# eskema_board_programacion.net
KiCad netlist of a schematic drawn in EAGLE
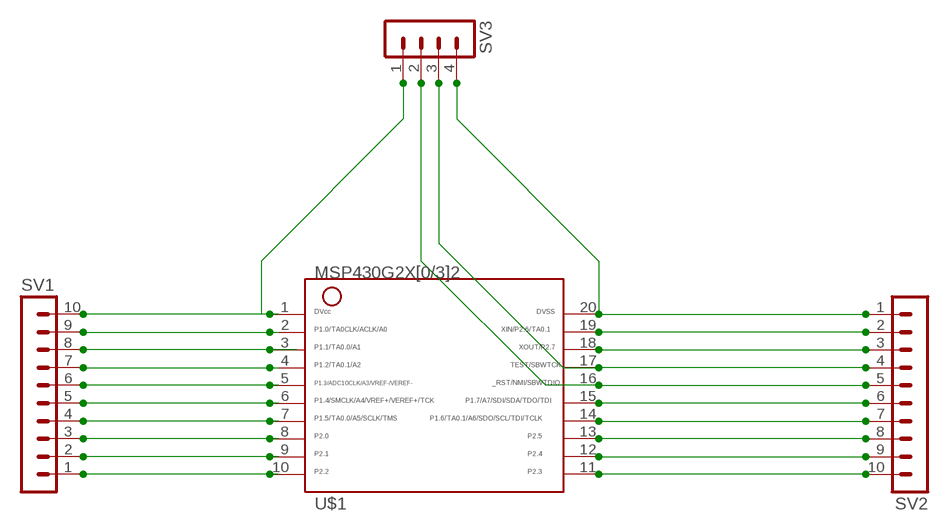
[diagram p0: schematic, sheet 1]

(export (version "E")
  (design (tool "Eeschema 10.0.6"))
  (components
    (comp (ref "SV1")
      (value "MA10-1")
      (footprint "eagle-import:MA10-1")
      (libsource (lib "eagle-import") (part "MA10-1"))
    )
    (comp (ref "SV2")
      (value "MA10-1")
      (footprint "eagle-import:MA10-1")
      (libsource (lib "eagle-import") (part "MA10-1"))
    )
    (comp (ref "SV3")
      (value "MA04-1")
      (footprint "eagle-import:MA04-1")
      (libsource (lib "eagle-import") (part "MA04-1"))
    )
    (comp (ref "U$1")
      (value "G2X[0/3]2---N20")
      (footprint "eagle-import:N20")
      (libsource (lib "eagle-import") (part "G2X[0/3]2---N20"))
    )
  )
  (nets
    (net (code "1") (name "Net-(SV1-Pad1)") (class "Default")
      (node (ref "SV1") (pin "1") (pinfunction "1_1") (pintype "passive"))
      (node (ref "U$1") (pin "10") (pinfunction "10_10") (pintype "bidirectional"))
    )
    (net (code "2") (name "Net-(SV1-Pad2)") (class "Default")
      (node (ref "SV1") (pin "2") (pinfunction "2_2") (pintype "passive"))
      (node (ref "U$1") (pin "9") (pinfunction "9_9") (pintype "bidirectional"))
    )
    (net (code "3") (name "Net-(SV1-Pad3)") (class "Default")
      (node (ref "SV1") (pin "3") (pinfunction "3_3") (pintype "passive"))
      (node (ref "U$1") (pin "8") (pinfunction "8_8") (pintype "bidirectional"))
    )
    (net (code "4") (name "Net-(SV1-Pad4)") (class "Default")
      (node (ref "SV1") (pin "4") (pinfunction "4_4") (pintype "passive"))
      (node (ref "U$1") (pin "7") (pinfunction "7_7") (pintype "bidirectional"))
    )
    (net (code "5") (name "Net-(SV1-Pad5)") (class "Default")
      (node (ref "SV1") (pin "5") (pinfunction "5_5") (pintype "passive"))
      (node (ref "U$1") (pin "6") (pinfunction "6_6") (pintype "bidirectional"))
    )
    (net (code "6") (name "Net-(SV1-Pad6)") (class "Default")
      (node (ref "SV1") (pin "6") (pinfunction "6_6") (pintype "passive"))
      (node (ref "U$1") (pin "5") (pinfunction "5_5") (pintype "bidirectional"))
    )
    (net (code "7") (name "Net-(SV1-Pad7)") (class "Default")
      (node (ref "SV1") (pin "7") (pinfunction "7_7") (pintype "passive"))
      (node (ref "U$1") (pin "4") (pinfunction "4_4") (pintype "bidirectional"))
    )
    (net (code "8") (name "Net-(SV1-Pad8)") (class "Default")
      (node (ref "SV1") (pin "8") (pinfunction "8_8") (pintype "passive"))
      (node (ref "U$1") (pin "3") (pinfunction "3_3") (pintype "bidirectional"))
    )
    (net (code "9") (name "Net-(SV1-Pad9)") (class "Default")
      (node (ref "SV1") (pin "9") (pinfunction "9_9") (pintype "passive"))
      (node (ref "U$1") (pin "2") (pinfunction "2_2") (pintype "bidirectional"))
    )
    (net (code "10") (name "Net-(SV1-Pad10)") (class "Default")
      (node (ref "SV1") (pin "10") (pinfunction "10_10") (pintype "passive"))
      (node (ref "SV3") (pin "1") (pinfunction "1_1") (pintype "passive"))
      (node (ref "U$1") (pin "1") (pinfunction "1_1") (pintype "bidirectional"))
    )
    (net (code "11") (name "Net-(SV2-Pad1)") (class "Default")
      (node (ref "SV2") (pin "1") (pinfunction "1_1") (pintype "passive"))
      (node (ref "SV3") (pin "4") (pinfunction "4_4") (pintype "passive"))
      (node (ref "U$1") (pin "20") (pinfunction "20_20") (pintype "bidirectional"))
    )
    (net (code "12") (name "Net-(SV2-Pad2)") (class "Default")
      (node (ref "SV2") (pin "2") (pinfunction "2_2") (pintype "passive"))
      (node (ref "U$1") (pin "19") (pinfunction "19_19") (pintype "bidirectional"))
    )
    (net (code "13") (name "Net-(SV2-Pad3)") (class "Default")
      (node (ref "SV2") (pin "3") (pinfunction "3_3") (pintype "passive"))
      (node (ref "U$1") (pin "18") (pinfunction "18_18") (pintype "bidirectional"))
    )
    (net (code "14") (name "Net-(SV2-Pad4)") (class "Default")
      (node (ref "SV2") (pin "4") (pinfunction "4_4") (pintype "passive"))
      (node (ref "SV3") (pin "3") (pinfunction "3_3") (pintype "passive"))
      (node (ref "U$1") (pin "17") (pinfunction "17_17") (pintype "bidirectional"))
    )
    (net (code "15") (name "Net-(SV2-Pad5)") (class "Default")
      (node (ref "SV2") (pin "5") (pinfunction "5_5") (pintype "passive"))
      (node (ref "SV3") (pin "2") (pinfunction "2_2") (pintype "passive"))
      (node (ref "U$1") (pin "16") (pinfunction "16_16") (pintype "bidirectional"))
    )
    (net (code "16") (name "Net-(SV2-Pad6)") (class "Default")
      (node (ref "SV2") (pin "6") (pinfunction "6_6") (pintype "passive"))
      (node (ref "U$1") (pin "15") (pinfunction "15_15") (pintype "bidirectional"))
    )
    (net (code "17") (name "Net-(SV2-Pad7)") (class "Default")
      (node (ref "SV2") (pin "7") (pinfunction "7_7") (pintype "passive"))
      (node (ref "U$1") (pin "14") (pinfunction "14_14") (pintype "bidirectional"))
    )
    (net (code "18") (name "Net-(SV2-Pad8)") (class "Default")
      (node (ref "SV2") (pin "8") (pinfunction "8_8") (pintype "passive"))
      (node (ref "U$1") (pin "13") (pinfunction "13_13") (pintype "bidirectional"))
    )
    (net (code "19") (name "Net-(SV2-Pad9)") (class "Default")
      (node (ref "SV2") (pin "9") (pinfunction "9_9") (pintype "passive"))
      (node (ref "U$1") (pin "12") (pinfunction "12_12") (pintype "bidirectional"))
    )
    (net (code "20") (name "Net-(SV2-Pad10)") (class "Default")
      (node (ref "SV2") (pin "10") (pinfunction "10_10") (pintype "passive"))
      (node (ref "U$1") (pin "11") (pinfunction "11_11") (pintype "bidirectional"))
    )
  )
)
